# cameraSliderInSession.net
KiCad netlist of a schematic drawn in EAGLE
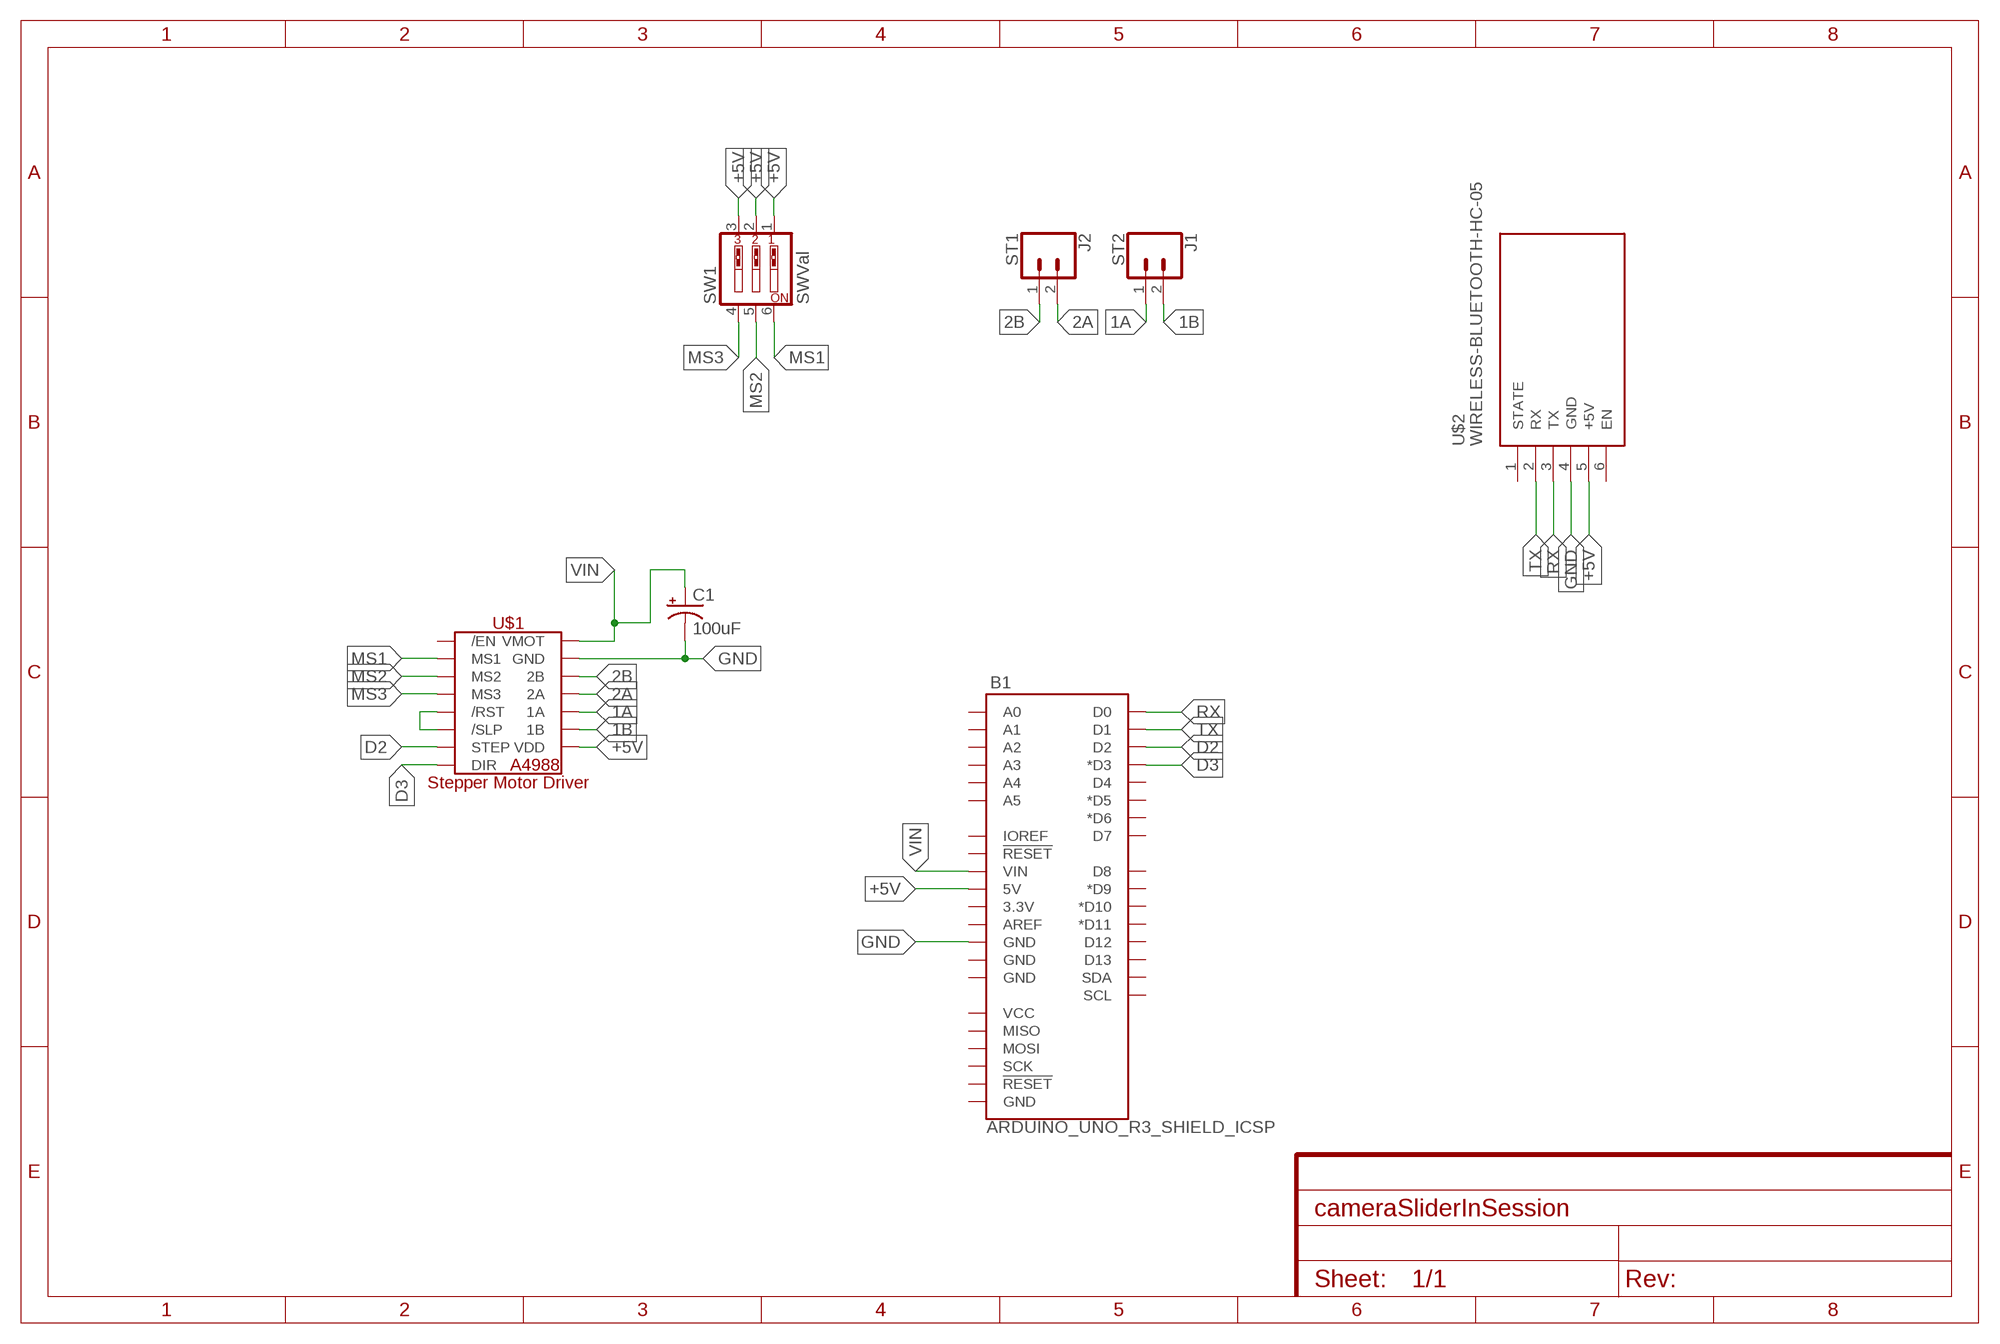
[diagram p0: schematic, sheet 1]

(export (version "E")
  (design (tool "Eeschema 10.0.6"))
  (components
    (comp (ref "B1")
      (value "ARDUINO_UNO_R3_SHIELD_ICSP")
      (footprint "eagle-import:UNO_R3_SHIELD_ICSP")
      (libsource (lib "eagle-import") (part "ARDUINO_UNO_R3_SHIELD_ICSP"))
    )
    (comp (ref "C1")
      (value "100uF")
      (footprint "eagle-import:CPOL-RADIAL-2.5MM-6.5MM")
      (libsource (lib "eagle-import") (part "100UF-POLAR-RADIAL-2.5MM-25V-20%"))
    )
    (comp (ref "J1")
      (value "ST2")
      (footprint "eagle-import:SCREWTERMINAL-5MM-2")
      (libsource (lib "eagle-import") (part "CONN_025MM"))
    )
    (comp (ref "J2")
      (value "ST1")
      (footprint "eagle-import:SCREWTERMINAL-5MM-2")
      (libsource (lib "eagle-import") (part "CONN_025MM"))
    )
    (comp (ref "SW1")
      (value "SWVal")
      (footprint "eagle-import:EDG-03")
      (libsource (lib "eagle-import") (part "SW_DIP-3"))
    )
    (comp (ref "U$1")
      (value "A4988_STEP")
      (footprint "eagle-import:A4988_STEP")
      (libsource (lib "eagle-import") (part "A4988_STEP"))
    )
    (comp (ref "U$2")
      (value "WIRELESS-BLUETOOTH-HC-05")
      (footprint "eagle-import:WIRELESS-BLUETOOTH-HC-05")
      (libsource (lib "eagle-import") (part "WIRELESS-BLUETOOTH-HC-05"))
    )
  )
  (nets
    (net (code "1") (name "+5V") (class "Default")
      (node (ref "B1") (pin "5V") (pinfunction "5V_5V") (pintype "bidirectional"))
      (node (ref "SW1") (pin "1") (pinfunction "1_1") (pintype "passive"))
      (node (ref "SW1") (pin "2") (pinfunction "2_2") (pintype "passive"))
      (node (ref "SW1") (pin "3") (pinfunction "3_3") (pintype "passive"))
      (node (ref "U$1") (pin "VDD") (pinfunction "VDD_VDD") (pintype "bidirectional"))
      (node (ref "U$2") (pin "5") (pinfunction "+5V_5") (pintype "power_in"))
    )
    (net (code "2") (name "1A") (class "Default")
      (node (ref "J1") (pin "1") (pinfunction "1_1") (pintype "passive"))
      (node (ref "U$1") (pin "1A") (pinfunction "1A_1A") (pintype "bidirectional"))
    )
    (net (code "3") (name "1B") (class "Default")
      (node (ref "J1") (pin "2") (pinfunction "2_2") (pintype "passive"))
      (node (ref "U$1") (pin "1B") (pinfunction "1B_1B") (pintype "bidirectional"))
    )
    (net (code "4") (name "2A") (class "Default")
      (node (ref "J2") (pin "2") (pinfunction "2_2") (pintype "passive"))
      (node (ref "U$1") (pin "2A") (pinfunction "2A_2A") (pintype "bidirectional"))
    )
    (net (code "5") (name "2B") (class "Default")
      (node (ref "J2") (pin "1") (pinfunction "1_1") (pintype "passive"))
      (node (ref "U$1") (pin "2B") (pinfunction "2B_2B") (pintype "bidirectional"))
    )
    (net (code "6") (name "D2") (class "Default")
      (node (ref "B1") (pin "D2") (pinfunction "D2_D2") (pintype "bidirectional"))
      (node (ref "U$1") (pin "STEP") (pinfunction "STEP_STEP") (pintype "bidirectional"))
    )
    (net (code "7") (name "D3") (class "Default")
      (node (ref "B1") (pin "D3") (pinfunction "*D3_D3") (pintype "bidirectional"))
      (node (ref "U$1") (pin "DIR") (pinfunction "DIR_DIR") (pintype "bidirectional"))
    )
    (net (code "8") (name "GND") (class "Default")
      (node (ref "B1") (pin "GND@2") (pinfunction "GND_GND@2") (pintype "bidirectional"))
      (node (ref "C1") (pin "2") (pinfunction "-_2") (pintype "passive"))
      (node (ref "U$1") (pin "GND") (pinfunction "GND_GND") (pintype "bidirectional"))
      (node (ref "U$1") (pin "GND2") (pinfunction "GND_GND2") (pintype "bidirectional"))
      (node (ref "U$2") (pin "4") (pinfunction "GND_4") (pintype "power_in"))
    )
    (net (code "9") (name "MS1") (class "Default")
      (node (ref "SW1") (pin "6") (pinfunction "6_6") (pintype "passive"))
      (node (ref "U$1") (pin "MS1") (pinfunction "MS1_MS1") (pintype "bidirectional"))
    )
    (net (code "10") (name "MS2") (class "Default")
      (node (ref "SW1") (pin "5") (pinfunction "5_5") (pintype "passive"))
      (node (ref "U$1") (pin "MS2") (pinfunction "MS2_MS2") (pintype "bidirectional"))
    )
    (net (code "11") (name "MS3") (class "Default")
      (node (ref "SW1") (pin "4") (pinfunction "4_4") (pintype "passive"))
      (node (ref "U$1") (pin "MS3") (pinfunction "MS3_MS3") (pintype "bidirectional"))
    )
    (net (code "12") (name "Net-(U$1-Pad{slash}RST)") (class "Default")
      (node (ref "U$1") (pin "/RST") (pinfunction "/RST_/RST") (pintype "bidirectional"))
      (node (ref "U$1") (pin "/SLP") (pinfunction "/SLP_/SLP") (pintype "bidirectional"))
    )
    (net (code "13") (name "RX") (class "Default")
      (node (ref "B1") (pin "RX") (pinfunction "D0_RX") (pintype "bidirectional"))
      (node (ref "U$2") (pin "3") (pinfunction "TX_3") (pintype "bidirectional"))
    )
    (net (code "14") (name "TX") (class "Default")
      (node (ref "B1") (pin "TX") (pinfunction "D1_TX") (pintype "bidirectional"))
      (node (ref "U$2") (pin "2") (pinfunction "RX_2") (pintype "bidirectional"))
    )
    (net (code "15") (name "VIN") (class "Default")
      (node (ref "B1") (pin "VIN") (pinfunction "VIN_VIN") (pintype "bidirectional"))
      (node (ref "C1") (pin "1") (pinfunction "+_1") (pintype "passive"))
      (node (ref "U$1") (pin "VMOT") (pinfunction "VMOT_VMOT") (pintype "bidirectional"))
    )
    (net (code "16") (name "unconnected-(B1-*D5-PadD5)") (class "Default")
      (node (ref "B1") (pin "D5") (pinfunction "*D5_D5") (pintype "bidirectional"))
    )
    (net (code "17") (name "unconnected-(B1-*D6-PadD6)") (class "Default")
      (node (ref "B1") (pin "D6") (pinfunction "*D6_D6") (pintype "bidirectional"))
    )
    (net (code "18") (name "unconnected-(B1-*D9-PadD9)") (class "Default")
      (node (ref "B1") (pin "D9") (pinfunction "*D9_D9") (pintype "bidirectional"))
    )
    (net (code "19") (name "unconnected-(B1-*D10-PadD10)") (class "Default")
      (node (ref "B1") (pin "D10") (pinfunction "*D10_D10") (pintype "bidirectional"))
    )
    (net (code "20") (name "unconnected-(B1-*D11-PadD11)") (class "Default")
      (node (ref "B1") (pin "D11") (pinfunction "*D11_D11") (pintype "bidirectional"))
    )
    (net (code "21") (name "unconnected-(B1-GND-PadGND@0)") (class "Default")
      (node (ref "B1") (pin "GND@0") (pinfunction "GND_GND@0") (pintype "bidirectional"))
    )
    (net (code "22") (name "unconnected-(B1-GND-PadGND@1)") (class "Default")
      (node (ref "B1") (pin "GND@1") (pinfunction "GND_GND@1") (pintype "bidirectional"))
    )
    (net (code "23") (name "unconnected-(B1-GND-PadGND_ICSP)") (class "Default")
      (node (ref "B1") (pin "GND_ICSP") (pinfunction "GND_GND_ICSP") (pintype "bidirectional"))
    )
    (net (code "24") (name "unconnected-(B1-Pad3.3V)") (class "Default")
      (node (ref "B1") (pin "3.3V") (pinfunction "3.3V_3.3V") (pintype "bidirectional"))
    )
    (net (code "25") (name "unconnected-(B1-PadA0)") (class "Default")
      (node (ref "B1") (pin "A0") (pinfunction "A0_A0") (pintype "bidirectional"))
    )
    (net (code "26") (name "unconnected-(B1-PadA1)") (class "Default")
      (node (ref "B1") (pin "A1") (pinfunction "A1_A1") (pintype "bidirectional"))
    )
    (net (code "27") (name "unconnected-(B1-PadA2)") (class "Default")
      (node (ref "B1") (pin "A2") (pinfunction "A2_A2") (pintype "bidirectional"))
    )
    (net (code "28") (name "unconnected-(B1-PadA3)") (class "Default")
      (node (ref "B1") (pin "A3") (pinfunction "A3_A3") (pintype "bidirectional"))
    )
    (net (code "29") (name "unconnected-(B1-PadA4)") (class "Default")
      (node (ref "B1") (pin "A4") (pinfunction "A4_A4") (pintype "bidirectional"))
    )
    (net (code "30") (name "unconnected-(B1-PadA5)") (class "Default")
      (node (ref "B1") (pin "A5") (pinfunction "A5_A5") (pintype "bidirectional"))
    )
    (net (code "31") (name "unconnected-(B1-PadAREF)") (class "Default")
      (node (ref "B1") (pin "AREF") (pinfunction "AREF_AREF") (pintype "bidirectional"))
    )
    (net (code "32") (name "unconnected-(B1-PadD4)") (class "Default")
      (node (ref "B1") (pin "D4") (pinfunction "D4_D4") (pintype "bidirectional"))
    )
    (net (code "33") (name "unconnected-(B1-PadD7)") (class "Default")
      (node (ref "B1") (pin "D7") (pinfunction "D7_D7") (pintype "bidirectional"))
    )
    (net (code "34") (name "unconnected-(B1-PadD8)") (class "Default")
      (node (ref "B1") (pin "D8") (pinfunction "D8_D8") (pintype "bidirectional"))
    )
    (net (code "35") (name "unconnected-(B1-PadD12)") (class "Default")
      (node (ref "B1") (pin "D12") (pinfunction "D12_D12") (pintype "bidirectional"))
    )
    (net (code "36") (name "unconnected-(B1-PadD13)") (class "Default")
      (node (ref "B1") (pin "D13") (pinfunction "D13_D13") (pintype "bidirectional"))
    )
    (net (code "37") (name "unconnected-(B1-PadIOREF)") (class "Default")
      (node (ref "B1") (pin "IOREF") (pinfunction "IOREF_IOREF") (pintype "bidirectional"))
    )
    (net (code "38") (name "unconnected-(B1-PadMISO)") (class "Default")
      (node (ref "B1") (pin "MISO") (pinfunction "MISO_MISO") (pintype "bidirectional"))
    )
    (net (code "39") (name "unconnected-(B1-PadMOSI)") (class "Default")
      (node (ref "B1") (pin "MOSI") (pinfunction "MOSI_MOSI") (pintype "bidirectional"))
    )
    (net (code "40") (name "unconnected-(B1-PadSCK)") (class "Default")
      (node (ref "B1") (pin "SCK") (pinfunction "SCK_SCK") (pintype "bidirectional"))
    )
    (net (code "41") (name "unconnected-(B1-PadSCL)") (class "Default")
      (node (ref "B1") (pin "SCL") (pinfunction "SCL_SCL") (pintype "bidirectional"))
    )
    (net (code "42") (name "unconnected-(B1-PadSDA)") (class "Default")
      (node (ref "B1") (pin "SDA") (pinfunction "SDA_SDA") (pintype "bidirectional"))
    )
    (net (code "43") (name "unconnected-(B1-VCC-Pad5V_ICSP)") (class "Default")
      (node (ref "B1") (pin "5V_ICSP") (pinfunction "VCC_5V_ICSP") (pintype "bidirectional"))
    )
    (net (code "44") (name "unconnected-(B1-~{RESET}-PadRES)") (class "Default")
      (node (ref "B1") (pin "RES") (pinfunction "~{RESET}_RES") (pintype "bidirectional"))
    )
    (net (code "45") (name "unconnected-(B1-~{RESET}-PadRST_ICSP)") (class "Default")
      (node (ref "B1") (pin "RST_ICSP") (pinfunction "~{RESET}_RST_ICSP") (pintype "bidirectional"))
    )
    (net (code "46") (name "unconnected-(U$1-Pad{slash}EN)") (class "Default")
      (node (ref "U$1") (pin "/EN") (pinfunction "/EN_/EN") (pintype "bidirectional"))
    )
    (net (code "47") (name "unconnected-(U$2-EN-Pad6)") (class "Default")
      (node (ref "U$2") (pin "6") (pinfunction "EN_6") (pintype "bidirectional"))
    )
    (net (code "48") (name "unconnected-(U$2-STATE-Pad1)") (class "Default")
      (node (ref "U$2") (pin "1") (pinfunction "STATE_1") (pintype "bidirectional"))
    )
  )
)
